# smoothieboard-alt-p1.net
KiCad netlist of a schematic drawn in Altium Designer
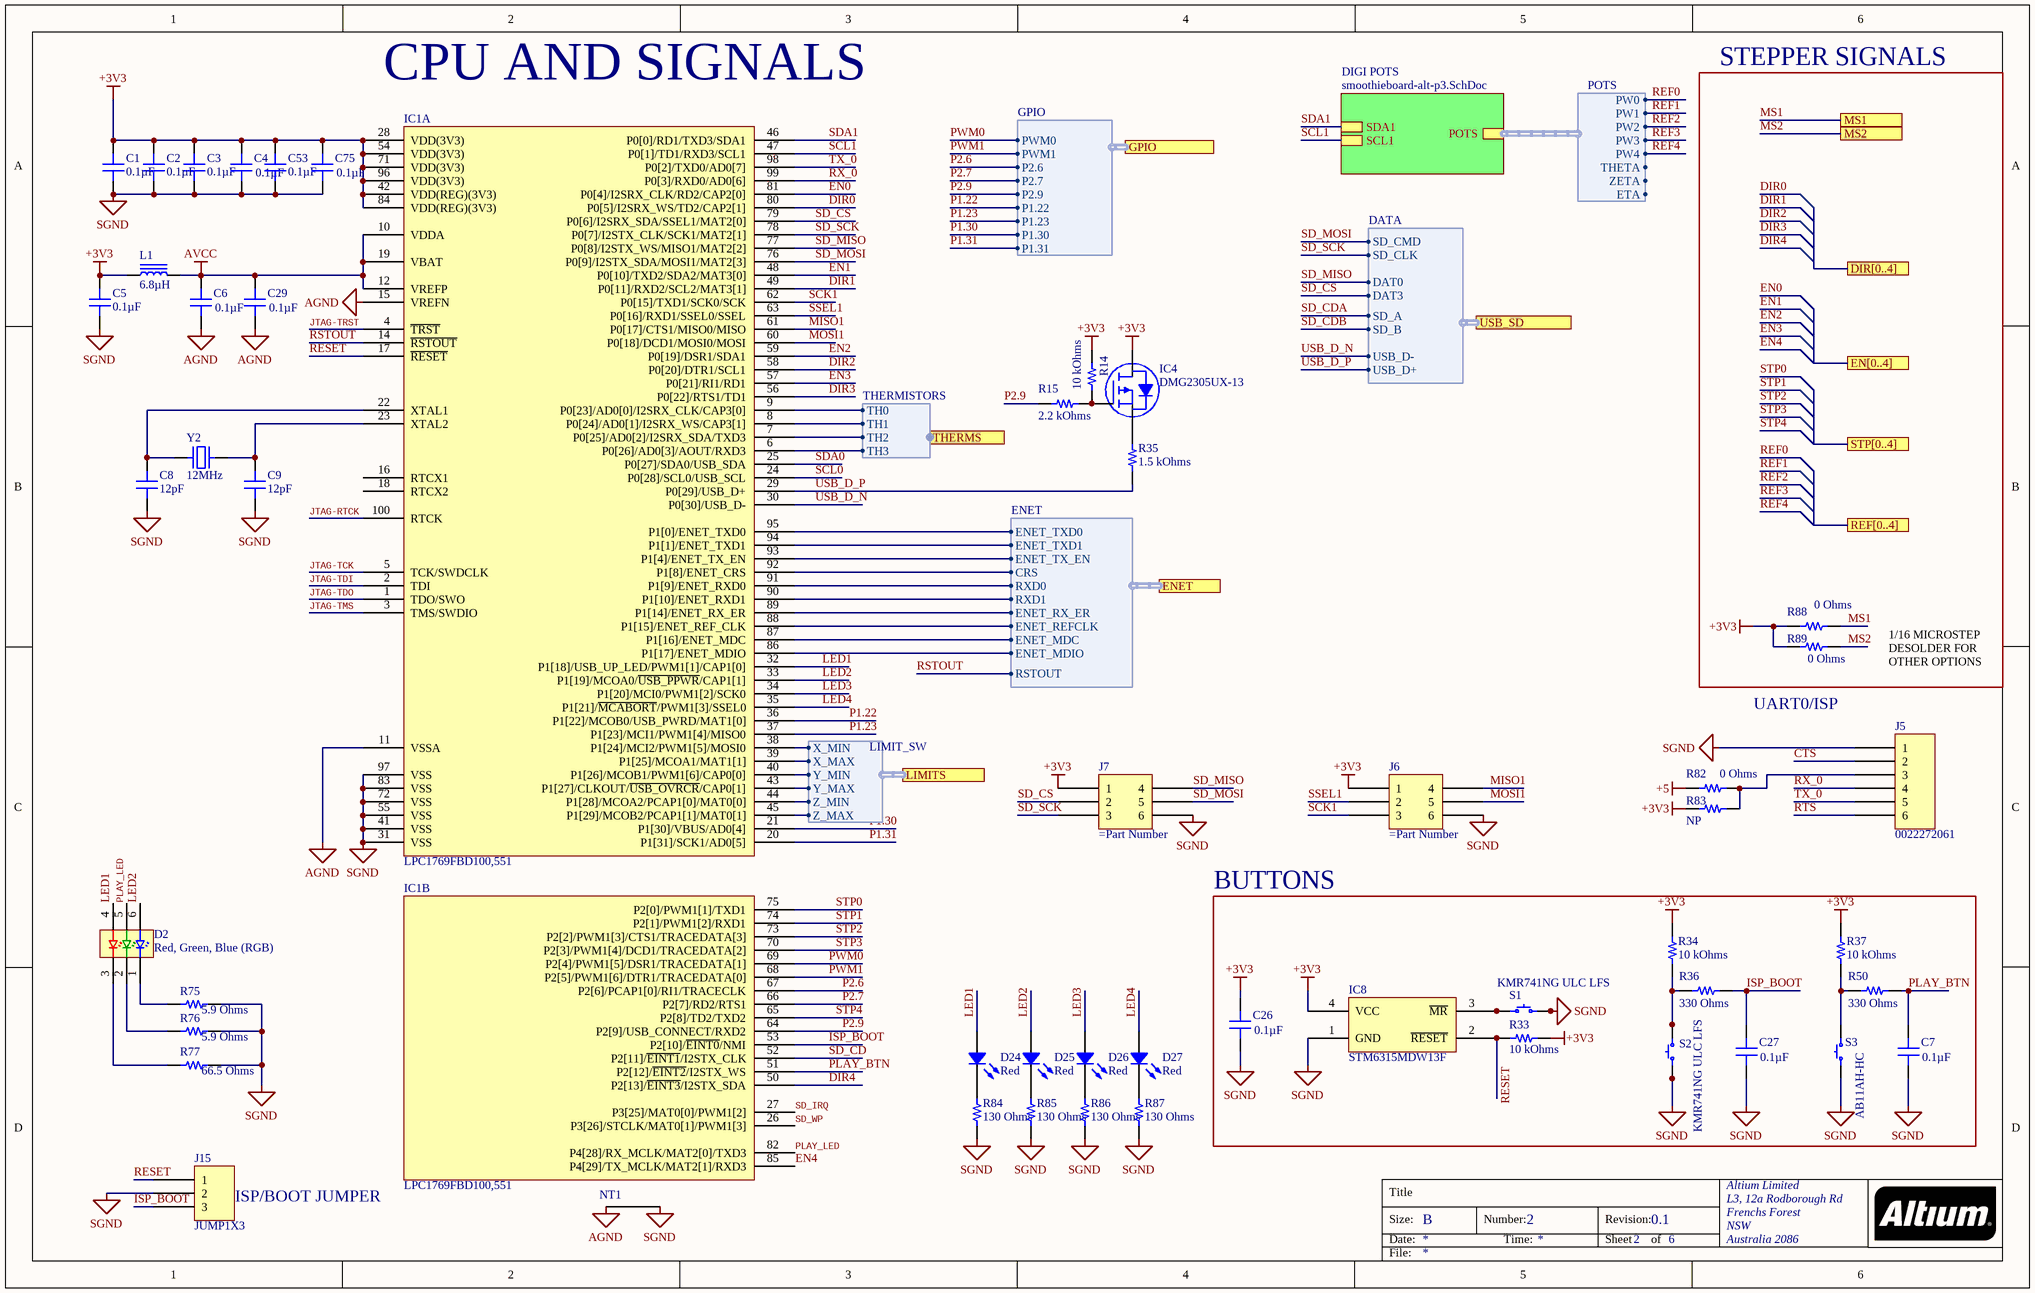
[diagram p0: smoothieboard-alt-p1.SchDoc]

(export (version "E")
  (design (tool "Eeschema 10.0.6"))
  (components
    (comp (ref "C1")
      (value "0.1µF")
      (footprint "CAP 0402_1005")
      (description "CAP CER 0.1UF 6.3V X5R 0402")
      (fields (field (name "PART NUMBER") "CC0402MRX5R5BB104") (field (name "MANUFACTURER") "Yageo"))
      (libsource (lib "CAL") (part "Capacitor"))
    )
    (comp (ref "C2")
      (value "0.1µF")
      (footprint "CAP 0402_1005")
      (description "CAP CER 0.1UF 6.3V X5R 0402")
      (fields (field (name "PART NUMBER") "CC0402MRX5R5BB104") (field (name "MANUFACTURER") "Yageo"))
      (libsource (lib "CAL") (part "Capacitor"))
    )
    (comp (ref "C3")
      (value "0.1µF")
      (footprint "CAP 0402_1005")
      (description "CAP CER 0.1UF 6.3V X5R 0402")
      (fields (field (name "PART NUMBER") "CC0402MRX5R5BB104") (field (name "MANUFACTURER") "Yageo"))
      (libsource (lib "CAL") (part "Capacitor"))
    )
    (comp (ref "C4")
      (value "0.1µF")
      (footprint "CAP 0402_1005")
      (description "CAP CER 0.1UF 6.3V X5R 0402")
      (fields (field (name "PART NUMBER") "CC0402MRX5R5BB104") (field (name "MANUFACTURER") "Yageo"))
      (libsource (lib "CAL") (part "Capacitor"))
    )
    (comp (ref "C5")
      (value "0.1µF")
      (footprint "CAP 0402_1005")
      (description "CAP CER 0.1UF 6.3V X5R 0402")
      (fields (field (name "PART NUMBER") "CC0402MRX5R5BB104") (field (name "MANUFACTURER") "Yageo"))
      (libsource (lib "CAL") (part "Capacitor"))
    )
    (comp (ref "C6")
      (value "0.1µF")
      (footprint "CAP 0402_1005")
      (description "CAP CER 0.1UF 6.3V X5R 0402")
      (fields (field (name "PART NUMBER") "CC0402MRX5R5BB104") (field (name "MANUFACTURER") "Yageo"))
      (libsource (lib "CAL") (part "Capacitor"))
    )
    (comp (ref "C7")
      (value "0.1µF")
      (footprint "CAP 0402_1005")
      (description "CAP CER 0.1UF 6.3V X5R 0402")
      (fields (field (name "PART NUMBER") "CC0402MRX5R5BB104") (field (name "MANUFACTURER") "Yageo"))
      (libsource (lib "CAL") (part "Capacitor"))
    )
    (comp (ref "C8")
      (value "12pF")
      (footprint "CAP 0402_1005")
      (description "CAP CER 12PF 10V NP0 0402")
      (fields (field (name "PART NUMBER") "C0402C120J8GAC7867") (field (name "MANUFACTURER") "KEMET"))
      (libsource (lib "CAL") (part "Capacitor"))
    )
    (comp (ref "C9")
      (value "12pF")
      (footprint "CAP 0402_1005")
      (description "CAP CER 12PF 10V NP0 0402")
      (fields (field (name "PART NUMBER") "C0402C120J8GAC7867") (field (name "MANUFACTURER") "KEMET"))
      (libsource (lib "CAL") (part "Capacitor"))
    )
    (comp (ref "C26")
      (value "0.1µF")
      (footprint "CAP 0402_1005")
      (description "CAP CER 0.1UF 6.3V X5R 0402")
      (fields (field (name "PART NUMBER") "CC0402MRX5R5BB104") (field (name "MANUFACTURER") "Yageo"))
      (libsource (lib "CAL") (part "Capacitor"))
    )
    (comp (ref "C27")
      (value "0.1µF")
      (footprint "CAP 0402_1005")
      (description "CAP CER 0.1UF 6.3V X5R 0402")
      (fields (field (name "PART NUMBER") "CC0402MRX5R5BB104") (field (name "MANUFACTURER") "Yageo"))
      (libsource (lib "CAL") (part "Capacitor"))
    )
    (comp (ref "C29")
      (value "0.1µF")
      (footprint "CAP 0402_1005")
      (description "CAP CER 0.1UF 6.3V X5R 0402")
      (fields (field (name "PART NUMBER") "CC0402MRX5R5BB104") (field (name "MANUFACTURER") "Yageo"))
      (libsource (lib "CAL") (part "Capacitor"))
    )
    (comp (ref "C53")
      (value "0.1µF")
      (footprint "CAP 0402_1005")
      (description "CAP CER 0.1UF 6.3V X5R 0402")
      (fields (field (name "PART NUMBER") "CC0402MRX5R5BB104") (field (name "MANUFACTURER") "Yageo"))
      (libsource (lib "CAL") (part "Capacitor"))
    )
    (comp (ref "C75")
      (value "0.1µF")
      (footprint "CAP 0402_1005")
      (description "CAP CER 0.1UF 6.3V X5R 0402")
      (fields (field (name "PART NUMBER") "CC0402MRX5R5BB104") (field (name "MANUFACTURER") "Yageo"))
      (libsource (lib "CAL") (part "Capacitor"))
    )
    (comp (ref "D2")
      (value "Red, Green, Blue (RGB)")
      (footprint "LED PLCC6-CREE 5.5X5.3MM")
      (description "LED RGB 6PLCC SMD")
      (fields
        (field (name "PART NUMBER") "SLV6A-FKB-CK1P1G1BB7R3R3")
        (field (name "MANUFACTURER") "Cree Inc.")
      )
      (libsource (lib "CAL") (part "RGB LED SLV6A"))
    )
    (comp (ref "D24")
      (value "Red")
      (footprint "LED 0603_1608 RED")
      (description "LED RED CLEAR 2SMD")
      (fields
        (field (name "PART NUMBER") "EAST16084RA0")
        (field (name "MANUFACTURER") "Everlight Electronics Co Ltd")
      )
      (libsource (lib "CAL") (part "LED"))
    )
    (comp (ref "D25")
      (value "Red")
      (footprint "LED 0603_1608 RED")
      (description "LED RED CLEAR 2SMD")
      (fields
        (field (name "PART NUMBER") "EAST16084RA0")
        (field (name "MANUFACTURER") "Everlight Electronics Co Ltd")
      )
      (libsource (lib "CAL") (part "LED"))
    )
    (comp (ref "D26")
      (value "Red")
      (footprint "LED 0603_1608 RED")
      (description "LED RED CLEAR 2SMD")
      (fields
        (field (name "PART NUMBER") "EAST16084RA0")
        (field (name "MANUFACTURER") "Everlight Electronics Co Ltd")
      )
      (libsource (lib "CAL") (part "LED"))
    )
    (comp (ref "D27")
      (value "Red")
      (footprint "LED 0603_1608 RED")
      (description "LED RED CLEAR 2SMD")
      (fields
        (field (name "PART NUMBER") "EAST16084RA0")
        (field (name "MANUFACTURER") "Everlight Electronics Co Ltd")
      )
      (libsource (lib "CAL") (part "LED"))
    )
    (comp (ref "IC1")
      (value "LPC1769FBD100,551")
      (footprint "NXP LQFP-100 14X14MM")
      (description "IC MCU 32BIT 512KB FLASH 100LQFP")
      (fields (field (name "MANUFACTURER") "NXP USA Inc."))
      (libsource (lib "CAL") (part "NXP LPC176X LQFP100"))
    )
    (comp (ref "IC4")
      (value "DMG2305UX-13")
      (footprint "DIODES SOT-23-3")
      (description "MOSFET P-CH 20V 4.2A SOT23")
      (fields (field (name "MANUFACTURER") "Diodes Incorporated"))
      (libsource (lib "CAL") (part "DIODES MOSFET P-CH SOT-23-3"))
    )
    (comp (ref "IC8")
      (value "STM6315MDW13F")
      (footprint "ST SOT-143-4")
      (description "IC SUPERVISOR 1 CHANNEL SOT143-4")
      (fields (field (name "MANUFACTURER") "STMicroelectronics"))
      (libsource (lib "CAL") (part "ST STM3615"))
    )
    (comp (ref "J5")
      (value "0022272061")
      (footprint "MOLEX KK 0022272061")
      (description "CONN HEADER VERT 6POS 2.54MM")
      (fields (field (name "MANUFACTURER") "Molex"))
      (libsource (lib "CAL") (part "6 Pin"))
    )
    (comp (ref "J6")
      (value "~")
      (footprint "smoothie-lib:PROG_PORT")
      (description "2x3 programming port")
      (libsource (lib "smoothie-lib") (part "PROG_PORT"))
    )
    (comp (ref "J7")
      (value "~")
      (footprint "smoothie-lib:PROG_PORT")
      (description "2x3 programming port")
      (libsource (lib "smoothie-lib") (part "PROG_PORT"))
    )
    (comp (ref "J15")
      (value "JUMP1X3")
      (footprint "smoothie-lib:JUMP1X3")
      (libsource (lib "smoothie-lib") (part "JUMP1X3"))
    )
    (comp (ref "L1")
      (value "6.8µH")
      (footprint "IND 0806_2016")
      (description "FIXED IND 6.8UH 910MA 468 MOHM")
      (fields
        (field (name "PART NUMBER") "VLS201612HBX-6R8M-1")
        (field (name "MANUFACTURER") "TDK Corporation")
      )
      (libsource (lib "CAL") (part "Inductor"))
    )
    (comp (ref "NT1")
      (value "NETTIE")
      (footprint "NETTIE")
      (description "Net tie point.")
      (libsource (lib "smoothie-lib") (part "NETTIE"))
    )
    (comp (ref "R14")
      (value "10 kOhms")
      (footprint "RES 0603_1608")
      (description "RES SMD 10K OHM 5% 1/4W 0603")
      (fields (field (name "PART NUMBER") "RCS060310K0JNEA") (field (name "MANUFACTURER") "Vishay Dale"))
      (libsource (lib "CAL") (part "Resistor"))
    )
    (comp (ref "R15")
      (value "2.2 kOhms")
      (footprint "RES 0402_1005")
      (description "RES SMD 0402 1/5W 1% 2.2K OHM")
      (fields (field (name "PART NUMBER") "SR0402FR-7T2K2L") (field (name "MANUFACTURER") "Yageo"))
      (libsource (lib "CAL") (part "Resistor"))
    )
    (comp (ref "R33")
      (value "10 kOhms")
      (footprint "RES 0603_1608")
      (description "RES SMD 10K OHM 5% 1/4W 0603")
      (fields (field (name "PART NUMBER") "RCS060310K0JNEA") (field (name "MANUFACTURER") "Vishay Dale"))
      (libsource (lib "CAL") (part "Resistor"))
    )
    (comp (ref "R34")
      (value "10 kOhms")
      (footprint "RES 0603_1608")
      (description "RES SMD 10K OHM 5% 1/4W 0603")
      (fields (field (name "PART NUMBER") "RCS060310K0JNEA") (field (name "MANUFACTURER") "Vishay Dale"))
      (libsource (lib "CAL") (part "Resistor"))
    )
    (comp (ref "R35")
      (value "1.5 kOhms")
      (footprint "RES 0402_1005")
      (description "RES SMD 1.5K OHM 1% 1/5W 0402")
      (fields (field (name "PART NUMBER") "CRCW04021K50FKEDHP") (field (name "MANUFACTURER") "Vishay Dale"))
      (libsource (lib "CAL") (part "Resistor"))
    )
    (comp (ref "R36")
      (value "330 Ohms")
      (footprint "RES 0603_1608")
      (description "RES SMD 330 OHM 5% 1/10W 0603")
      (fields
        (field (name "PART NUMBER") "ERJ-3GEYJ331V")
        (field (name "MANUFACTURER") "Panasonic Electronic Components")
      )
      (libsource (lib "CAL") (part "Resistor"))
    )
    (comp (ref "R37")
      (value "10 kOhms")
      (footprint "RES 0603_1608")
      (description "RES SMD 10K OHM 5% 1/4W 0603")
      (fields (field (name "PART NUMBER") "RCS060310K0JNEA") (field (name "MANUFACTURER") "Vishay Dale"))
      (libsource (lib "CAL") (part "Resistor"))
    )
    (comp (ref "R50")
      (value "330 Ohms")
      (footprint "RES 0603_1608")
      (description "RES SMD 330 OHM 5% 1/10W 0603")
      (fields
        (field (name "PART NUMBER") "ERJ-3GEYJ331V")
        (field (name "MANUFACTURER") "Panasonic Electronic Components")
      )
      (libsource (lib "CAL") (part "Resistor"))
    )
    (comp (ref "R75")
      (value "5.9 Ohms")
      (footprint "RES 0402_1005")
      (description "RES SMD 5.9 OHM 1% 1/16W 0402")
      (fields (field (name "PART NUMBER") "CRCW04025R90FKED") (field (name "MANUFACTURER") "Vishay Dale"))
      (libsource (lib "CAL") (part "Resistor"))
    )
    (comp (ref "R76")
      (value "5.9 Ohms")
      (footprint "RES 0402_1005")
      (description "RES SMD 5.9 OHM 1% 1/16W 0402")
      (fields (field (name "PART NUMBER") "CRCW04025R90FKED") (field (name "MANUFACTURER") "Vishay Dale"))
      (libsource (lib "CAL") (part "Resistor"))
    )
    (comp (ref "R77")
      (value "66.5 Ohms")
      (footprint "RES 0402_1005")
      (description "RES SMD 66.5 OHM 1% 1/10W 0402")
      (fields
        (field (name "PART NUMBER") "ERJ-2RKF66R5X")
        (field (name "MANUFACTURER") "Panasonic Electronic Components")
      )
      (libsource (lib "CAL") (part "Resistor"))
    )
    (comp (ref "R82")
      (value "0 Ohms")
      (footprint "RES 0603_1608")
      (description "RES SMD 0 OHM JUMPER 1/4W 0603")
      (fields (field (name "PART NUMBER") "CRCW06030000Z0EAHP") (field (name "MANUFACTURER") "Vishay Dale"))
      (libsource (lib "CAL") (part "Resistor"))
    )
    (comp (ref "R83")
      (value "NP")
      (footprint "RES 0603_1608")
      (description "RES SMD 0 OHM JUMPER 1/4W 0603")
      (fields (field (name "PART NUMBER") "CRCW06030000Z0EAHP") (field (name "MANUFACTURER") "Vishay Dale"))
      (libsource (lib "CAL") (part "Resistor"))
    )
    (comp (ref "R84")
      (value "130 Ohms")
      (footprint "RES 0402_1005")
      (description "RES SMD 130 OHM 5% 1/5W 0402")
      (fields
        (field (name "PART NUMBER") "ERJ-PA2J131X")
        (field (name "MANUFACTURER") "Panasonic Electronic Components")
      )
      (libsource (lib "CAL") (part "Resistor"))
    )
    (comp (ref "R85")
      (value "130 Ohms")
      (footprint "RES 0402_1005")
      (description "RES SMD 130 OHM 5% 1/5W 0402")
      (fields
        (field (name "PART NUMBER") "ERJ-PA2J131X")
        (field (name "MANUFACTURER") "Panasonic Electronic Components")
      )
      (libsource (lib "CAL") (part "Resistor"))
    )
    (comp (ref "R86")
      (value "130 Ohms")
      (footprint "RES 0402_1005")
      (description "RES SMD 130 OHM 5% 1/5W 0402")
      (fields
        (field (name "PART NUMBER") "ERJ-PA2J131X")
        (field (name "MANUFACTURER") "Panasonic Electronic Components")
      )
      (libsource (lib "CAL") (part "Resistor"))
    )
    (comp (ref "R87")
      (value "130 Ohms")
      (footprint "RES 0402_1005")
      (description "RES SMD 130 OHM 5% 1/5W 0402")
      (fields
        (field (name "PART NUMBER") "ERJ-PA2J131X")
        (field (name "MANUFACTURER") "Panasonic Electronic Components")
      )
      (libsource (lib "CAL") (part "Resistor"))
    )
    (comp (ref "R88")
      (value "0 Ohms")
      (footprint "RES 0603_1608")
      (description "RES SMD 0 OHM JUMPER 1/4W 0603")
      (fields (field (name "PART NUMBER") "CRCW06030000Z0EAHP") (field (name "MANUFACTURER") "Vishay Dale"))
      (libsource (lib "CAL") (part "Resistor"))
    )
    (comp (ref "R89")
      (value "0 Ohms")
      (footprint "RES 0603_1608")
      (description "RES SMD 0 OHM JUMPER 1/4W 0603")
      (fields (field (name "PART NUMBER") "CRCW06030000Z0EAHP") (field (name "MANUFACTURER") "Vishay Dale"))
      (libsource (lib "CAL") (part "Resistor"))
    )
    (comp (ref "S1")
      (value "KMR741NG ULC LFS")
      (footprint "C&K KMR7")
      (description "SWITCH TACTILE SPST-NO 50MA 32V")
      (fields (field (name "MANUFACTURER") "C&K"))
      (libsource (lib "CAL") (part "SPST-NO 4 PIN"))
    )
    (comp (ref "S2")
      (value "KMR741NG ULC LFS")
      (footprint "C&K KMR7")
      (description "SWITCH TACTILE SPST-NO 50MA 32V")
      (fields (field (name "MANUFACTURER") "C&K"))
      (libsource (lib "CAL") (part "SPST-NO 4 PIN"))
    )
    (comp (ref "S3")
      (value "AB11AH-HC")
      (footprint "NKK AB11AH-HC")
      (description "SWITCH PUSH SPST-NO 0.4VA 28V")
      (fields (field (name "MANUFACTURER") "NKK Switches"))
      (libsource (lib "CAL") (part "SPST-NO 2 PIN"))
    )
    (comp (ref "Y2")
      (value "12MHz")
      (footprint "KYOCERA CX3225GB")
      (description "CRYSTAL 12.0000MHZ 12PF SMD")
      (fields
        (field (name "PART NUMBER") "CX3225GB12000H0KPSC1")
        (field (name "MANUFACTURER") "Kyocera International Inc. Electronic Components")
      )
      (libsource (lib "CAL") (part "Kyocera Crystal CX3225GB"))
    )
  )
  (nets
    (net (code "7") (name "+3V3") (class "Default")
      (node (ref "C1") (pin "2") (pinfunction "2_2") (pintype "passive"))
      (node (ref "C2") (pin "2") (pinfunction "2_2") (pintype "passive"))
      (node (ref "C26") (pin "2") (pinfunction "2_2") (pintype "passive"))
      (node (ref "C3") (pin "2") (pinfunction "2_2") (pintype "passive"))
      (node (ref "C4") (pin "2") (pinfunction "2_2") (pintype "passive"))
      (node (ref "C5") (pin "2") (pinfunction "2_2") (pintype "passive"))
      (node (ref "C53") (pin "2") (pinfunction "2_2") (pintype "passive"))
      (node (ref "C75") (pin "2") (pinfunction "2_2") (pintype "passive"))
      (node (ref "IC1") (pin "28") (pinfunction "VDD(3V3)_28") (pintype "passive"))
      (node (ref "IC1") (pin "42") (pinfunction "VDD(REG)(3V3)_42") (pintype "passive"))
      (node (ref "IC1") (pin "54") (pinfunction "VDD(3V3)_54") (pintype "passive"))
      (node (ref "IC1") (pin "71") (pinfunction "VDD(3V3)_71") (pintype "passive"))
      (node (ref "IC1") (pin "84") (pinfunction "VDD(REG)(3V3)_84") (pintype "passive"))
      (node (ref "IC1") (pin "96") (pinfunction "VDD(3V3)_96") (pintype "passive"))
      (node (ref "IC4") (pin "3") (pinfunction "D_3") (pintype "passive"))
      (node (ref "IC8") (pin "4") (pinfunction "VCC_4") (pintype "passive"))
      (node (ref "J6") (pin "1") (pinfunction "1_1") (pintype "passive"))
      (node (ref "J7") (pin "1") (pinfunction "1_1") (pintype "passive"))
      (node (ref "L1") (pin "1") (pinfunction "1_1") (pintype "passive"))
      (node (ref "R14") (pin "1") (pinfunction "1_1") (pintype "passive"))
      (node (ref "R33") (pin "2") (pinfunction "2_2") (pintype "passive"))
      (node (ref "R34") (pin "1") (pinfunction "1_1") (pintype "passive"))
      (node (ref "R37") (pin "1") (pinfunction "1_1") (pintype "passive"))
      (node (ref "R83") (pin "1") (pinfunction "1_1") (pintype "passive"))
      (node (ref "R88") (pin "1") (pinfunction "1_1") (pintype "passive"))
      (node (ref "R89") (pin "1") (pinfunction "1_1") (pintype "passive"))
    )
    (net (code "8") (name "+5") (class "Default")
      (node (ref "R82") (pin "1") (pinfunction "1_1") (pintype "passive"))
    )
    (net (code "9") (name "/CRS") (class "Default")
      (node (ref "IC1") (pin "92") (pinfunction "P1[8]/ENET_CRS_92") (pintype "passive"))
    )
    (net (code "10") (name "/CTS") (class "Default")
      (node (ref "J5") (pin "2") (pinfunction "2_2") (pintype "passive"))
    )
    (net (code "11") (name "/DIR0") (class "Default")
      (node (ref "IC1") (pin "80") (pinfunction "P0[5]/I2SRX_WS/TD2/CAP2[1]_80") (pintype "passive"))
    )
    (net (code "12") (name "/DIR1") (class "Default")
      (node (ref "IC1") (pin "49") (pinfunction "P0[11]/RXD2/SCL2/MAT3[1]_49") (pintype "passive"))
    )
    (net (code "13") (name "/DIR2") (class "Default")
      (node (ref "IC1") (pin "58") (pinfunction "P0[20]/DTR1/SCL1_58") (pintype "passive"))
    )
    (net (code "14") (name "/DIR3") (class "Default")
      (node (ref "IC1") (pin "56") (pinfunction "P0[22]/RTS1/TD1_56") (pintype "passive"))
    )
    (net (code "15") (name "/DIR4") (class "Default")
      (node (ref "IC1") (pin "50") (pinfunction "P2[13]/~{EINT3}/I2STX_SDA_50") (pintype "passive"))
    )
    (net (code "17") (name "/EN0") (class "Default")
      (node (ref "IC1") (pin "81") (pinfunction "P0[4]/I2SRX_CLK/RD2/CAP2[0]_81") (pintype "passive"))
    )
    (net (code "18") (name "/EN1") (class "Default")
      (node (ref "IC1") (pin "48") (pinfunction "P0[10]/TXD2/SDA2/MAT3[0]_48") (pintype "passive"))
    )
    (net (code "19") (name "/EN2") (class "Default")
      (node (ref "IC1") (pin "59") (pinfunction "P0[19]/DSR1/SDA1_59") (pintype "passive"))
    )
    (net (code "20") (name "/EN3") (class "Default")
      (node (ref "IC1") (pin "57") (pinfunction "P0[21]/RI1/RD1_57") (pintype "passive"))
    )
    (net (code "21") (name "/EN4") (class "Default")
      (node (ref "IC1") (pin "85") (pinfunction "P4[29]/TX_MCLK/MAT2[1]/RXD3_85") (pintype "passive"))
    )
    (net (code "22") (name "/ENET_MDC") (class "Default")
      (node (ref "IC1") (pin "87") (pinfunction "P1[16]/ENET_MDC_87") (pintype "passive"))
    )
    (net (code "23") (name "/ENET_MDIO") (class "Default")
      (node (ref "IC1") (pin "86") (pinfunction "P1[17]/ENET_MDIO_86") (pintype "passive"))
    )
    (net (code "24") (name "/ENET_REFCLK") (class "Default")
      (node (ref "IC1") (pin "88") (pinfunction "P1[15]/ENET_REF_CLK_88") (pintype "passive"))
    )
    (net (code "25") (name "/ENET_RX_ER") (class "Default")
      (node (ref "IC1") (pin "89") (pinfunction "P1[14]/ENET_RX_ER_89") (pintype "passive"))
    )
    (net (code "26") (name "/ENET_TXD0") (class "Default")
      (node (ref "IC1") (pin "95") (pinfunction "P1[0]/ENET_TXD0_95") (pintype "passive"))
    )
    (net (code "27") (name "/ENET_TXD1") (class "Default")
      (node (ref "IC1") (pin "94") (pinfunction "P1[1]/ENET_TXD1_94") (pintype "passive"))
    )
    (net (code "28") (name "/ENET_TX_EN") (class "Default")
      (node (ref "IC1") (pin "93") (pinfunction "P1[4]/ENET_TX_EN_93") (pintype "passive"))
    )
    (net (code "30") (name "/ISP_BOOT") (class "Default")
      (node (ref "C27") (pin "2") (pinfunction "2_2") (pintype "passive"))
      (node (ref "IC1") (pin "53") (pinfunction "P2[10]/~{EINT0}/NMI_53") (pintype "passive"))
      (node (ref "J15") (pin "3") (pinfunction "3_3") (pintype "passive"))
      (node (ref "R36") (pin "1") (pinfunction "1_1") (pintype "passive"))
    )
    (net (code "31") (name "/JTAG-RTCK") (class "Default")
      (node (ref "IC1") (pin "100") (pinfunction "RTCK_100") (pintype "passive"))
    )
    (net (code "32") (name "/JTAG-TCK") (class "Default")
      (node (ref "IC1") (pin "5") (pinfunction "TCK/SWDCLK_5") (pintype "passive"))
    )
    (net (code "33") (name "/JTAG-TDI") (class "Default")
      (node (ref "IC1") (pin "2") (pinfunction "TDI_2") (pintype "passive"))
    )
    (net (code "34") (name "/JTAG-TDO") (class "Default")
      (node (ref "IC1") (pin "1") (pinfunction "TDO/SWO_1") (pintype "passive"))
    )
    (net (code "35") (name "/JTAG-TMS") (class "Default")
      (node (ref "IC1") (pin "3") (pinfunction "TMS/SWDIO_3") (pintype "passive"))
    )
    (net (code "36") (name "/JTAG-TRST") (class "Default")
      (node (ref "IC1") (pin "4") (pinfunction "~{TRST}_4") (pintype "passive"))
    )
    (net (code "37") (name "/LED1") (class "Default")
      (node (ref "D2") (pin "4") (pinfunction "A3_4") (pintype "passive"))
      (node (ref "D24") (pin "1") (pinfunction "1_1") (pintype "passive"))
      (node (ref "IC1") (pin "32") (pinfunction "P1[18]/USB_UP_LED/PWM1[1]/CAP1[0]_32") (pintype "passive"))
    )
    (net (code "38") (name "/LED2") (class "Default")
      (node (ref "D2") (pin "6") (pinfunction "A1_6") (pintype "passive"))
      (node (ref "D25") (pin "1") (pinfunction "1_1") (pintype "passive"))
      (node (ref "IC1") (pin "33") (pinfunction "P1[19]/MCOA0/~{USB_PPWR}/CAP1[1]_33") (pintype "passive"))
    )
    (net (code "39") (name "/LED3") (class "Default")
      (node (ref "D26") (pin "1") (pinfunction "1_1") (pintype "passive"))
      (node (ref "IC1") (pin "34") (pinfunction "P1[20]/MCI0/PWM1[2]/SCK0_34") (pintype "passive"))
    )
    (net (code "40") (name "/LED4") (class "Default")
      (node (ref "D27") (pin "1") (pinfunction "1_1") (pintype "passive"))
      (node (ref "IC1") (pin "35") (pinfunction "P1[21]/~{MCABORT}/PWM1[3]/SSEL0_35") (pintype "passive"))
    )
    (net (code "41") (name "/MISO1") (class "Default")
      (node (ref "IC1") (pin "61") (pinfunction "P0[17]/CTS1/MISO0/MISO_61") (pintype "passive"))
      (node (ref "J6") (pin "4") (pinfunction "4_4") (pintype "passive"))
    )
    (net (code "42") (name "/MOSI1") (class "Default")
      (node (ref "IC1") (pin "60") (pinfunction "P0[18]/DCD1/MOSI0/MOSI_60") (pintype "passive"))
      (node (ref "J6") (pin "5") (pinfunction "5_5") (pintype "passive"))
    )
    (net (code "43") (name "/MS1") (class "Default")
      (node (ref "R88") (pin "2") (pinfunction "2_2") (pintype "passive"))
    )
    (net (code "44") (name "/MS2") (class "Default")
      (node (ref "R89") (pin "2") (pinfunction "2_2") (pintype "passive"))
    )
    (net (code "45") (name "/P1.22") (class "Default")
      (node (ref "IC1") (pin "36") (pinfunction "P1[22]/MCOB0/USB_PWRD/MAT1[0]_36") (pintype "passive"))
    )
    (net (code "46") (name "/P1.23") (class "Default")
      (node (ref "IC1") (pin "37") (pinfunction "P1[23]/MCI1/PWM1[4]/MISO0_37") (pintype "passive"))
    )
    (net (code "47") (name "/P1.30") (class "Default")
      (node (ref "IC1") (pin "21") (pinfunction "P1[30]/VBUS/AD0[4]_21") (pintype "passive"))
    )
    (net (code "48") (name "/P1.31") (class "Default")
      (node (ref "IC1") (pin "20") (pinfunction "P1[31]/SCK1/AD0[5]_20") (pintype "passive"))
    )
    (net (code "49") (name "/P2.6") (class "Default")
      (node (ref "IC1") (pin "67") (pinfunction "P2[6]/PCAP1[0]/RI1/TRACECLK_67") (pintype "passive"))
    )
    (net (code "50") (name "/P2.7") (class "Default")
      (node (ref "IC1") (pin "66") (pinfunction "P2[7]/RD2/RTS1_66") (pintype "passive"))
    )
    (net (code "51") (name "/P2.9") (class "Default")
      (node (ref "IC1") (pin "64") (pinfunction "P2[9]/USB_CONNECT/RXD2_64") (pintype "passive"))
      (node (ref "R15") (pin "2") (pinfunction "2_2") (pintype "passive"))
    )
    (net (code "52") (name "/PLAY_BTN") (class "Default")
      (node (ref "C7") (pin "2") (pinfunction "2_2") (pintype "passive"))
      (node (ref "IC1") (pin "51") (pinfunction "P2[12]/~{EINT2}/I2STX_WS_51") (pintype "passive"))
      (node (ref "R50") (pin "1") (pinfunction "1_1") (pintype "passive"))
    )
    (net (code "53") (name "/PLAY_LED") (class "Default")
      (node (ref "D2") (pin "5") (pinfunction "A2_5") (pintype "passive"))
      (node (ref "IC1") (pin "82") (pinfunction "P4[28]/RX_MCLK/MAT2[0]/TXD3_82") (pintype "passive"))
    )
    (net (code "54") (name "/PWM0") (class "Default")
      (node (ref "IC1") (pin "69") (pinfunction "P2[4]/PWM1[5]/DSR1/TRACEDATA[1]_69") (pintype "passive"))
    )
    (net (code "55") (name "/PWM1") (class "Default")
      (node (ref "IC1") (pin "68") (pinfunction "P2[5]/PWM1[6]/DTR1/TRACEDATA[0]_68") (pintype "passive"))
    )
    (net (code "62") (name "/RESET") (class "Default")
      (node (ref "IC1") (pin "17") (pinfunction "~{RESET}_17") (pintype "passive"))
      (node (ref "IC8") (pin "2") (pinfunction "~{RESET}_2") (pintype "passive"))
      (node (ref "J15") (pin "1") (pinfunction "1_1") (pintype "passive"))
      (node (ref "R33") (pin "1") (pinfunction "1_1") (pintype "passive"))
    )
    (net (code "63") (name "/RSTOUT") (class "Default")
      (node (ref "IC1") (pin "14") (pinfunction "~{RSTOUT}_14") (pintype "passive"))
    )
    (net (code "64") (name "/RTS") (class "Default")
      (node (ref "J5") (pin "6") (pinfunction "6_6") (pintype "passive"))
    )
    (net (code "65") (name "/RXD0") (class "Default")
      (node (ref "IC1") (pin "91") (pinfunction "P1[9]/ENET_RXD0_91") (pintype "passive"))
    )
    (net (code "66") (name "/RXD1") (class "Default")
      (node (ref "IC1") (pin "90") (pinfunction "P1[10]/ENET_RXD1_90") (pintype "passive"))
    )
    (net (code "67") (name "/RX_0") (class "Default")
      (node (ref "IC1") (pin "99") (pinfunction "P0[3]/RXD0/AD0[6]_99") (pintype "passive"))
      (node (ref "J5") (pin "4") (pinfunction "4_4") (pintype "passive"))
    )
    (net (code "68") (name "/SCK1") (class "Default")
      (node (ref "IC1") (pin "62") (pinfunction "P0[15]/TXD1/SCK0/SCK_62") (pintype "passive"))
      (node (ref "J6") (pin "3") (pinfunction "3_3") (pintype "passive"))
    )
    (net (code "69") (name "/SCL0") (class "Default")
      (node (ref "IC1") (pin "24") (pinfunction "P0[28]/SCL0/USB_SCL_24") (pintype "passive"))
    )
    (net (code "70") (name "/SCL1") (class "Default")
      (node (ref "IC1") (pin "47") (pinfunction "P0[1]/TD1/RXD3/SCL1_47") (pintype "passive"))
    )
    (net (code "71") (name "/SDA0") (class "Default")
      (node (ref "IC1") (pin "25") (pinfunction "P0[27]/SDA0/USB_SDA_25") (pintype "passive"))
    )
    (net (code "72") (name "/SDA1") (class "Default")
      (node (ref "IC1") (pin "46") (pinfunction "P0[0]/RD1/TXD3/SDA1_46") (pintype "passive"))
    )
    (net (code "73") (name "/SD_CD") (class "Default")
      (node (ref "IC1") (pin "52") (pinfunction "P2[11]/~{EINT1}/I2STX_CLK_52") (pintype "passive"))
    )
    (net (code "76") (name "/SD_CS") (class "Default")
      (node (ref "IC1") (pin "79") (pinfunction "P0[6]/I2SRX_SDA/SSEL1/MAT2[0]_79") (pintype "passive"))
      (node (ref "J7") (pin "2") (pinfunction "2_2") (pintype "passive"))
    )
    (net (code "77") (name "/SD_IRQ") (class "Default")
      (node (ref "IC1") (pin "27") (pinfunction "P3[25]/MAT0[0]/PWM1[2]_27") (pintype "passive"))
    )
    (net (code "78") (name "/SD_MISO") (class "Default")
      (node (ref "IC1") (pin "77") (pinfunction "P0[8]/I2STX_WS/MISO1/MAT2[2]_77") (pintype "passive"))
      (node (ref "J7") (pin "4") (pinfunction "4_4") (pintype "passive"))
    )
    (net (code "79") (name "/SD_MOSI") (class "Default")
      (node (ref "IC1") (pin "76") (pinfunction "P0[9]/I2STX_SDA/MOSI1/MAT2[3]_76") (pintype "passive"))
      (node (ref "J7") (pin "5") (pinfunction "5_5") (pintype "passive"))
    )
    (net (code "80") (name "/SD_SCK") (class "Default")
      (node (ref "IC1") (pin "78") (pinfunction "P0[7]/I2STX_CLK/SCK1/MAT2[1]_78") (pintype "passive"))
      (node (ref "J7") (pin "3") (pinfunction "3_3") (pintype "passive"))
    )
    (net (code "81") (name "/SD_WP") (class "Default")
      (node (ref "IC1") (pin "26") (pinfunction "P3[26]/STCLK/MAT0[1]/PWM1[3]_26") (pintype "passive"))
    )
    (net (code "82") (name "/SSEL1") (class "Default")
      (node (ref "IC1") (pin "63") (pinfunction "P0[16]/RXD1/SSEL0/SSEL_63") (pintype "passive"))
      (node (ref "J6") (pin "2") (pinfunction "2_2") (pintype "passive"))
    )
    (net (code "83") (name "/STP0") (class "Default")
      (node (ref "IC1") (pin "75") (pinfunction "P2[0]/PWM1[1]/TXD1_75") (pintype "passive"))
    )
    (net (code "84") (name "/STP1") (class "Default")
      (node (ref "IC1") (pin "74") (pinfunction "P2[1]/PWM1[2]/RXD1_74") (pintype "passive"))
    )
    (net (code "85") (name "/STP2") (class "Default")
      (node (ref "IC1") (pin "73") (pinfunction "P2[2]/PWM1[3]/CTS1/TRACEDATA[3]_73") (pintype "passive"))
    )
    (net (code "86") (name "/STP3") (class "Default")
      (node (ref "IC1") (pin "70") (pinfunction "P2[3]/PWM1[4]/DCD1/TRACEDATA[2]_70") (pintype "passive"))
    )
    (net (code "87") (name "/STP4") (class "Default")
      (node (ref "IC1") (pin "65") (pinfunction "P2[8]/TD2/TXD2_65") (pintype "passive"))
    )
    (net (code "89") (name "/TH0") (class "Default")
      (node (ref "IC1") (pin "9") (pinfunction "P0[23]/AD0[0]/I2SRX_CLK/CAP3[0]_9") (pintype "passive"))
    )
    (net (code "90") (name "/TH1") (class "Default")
      (node (ref "IC1") (pin "8") (pinfunction "P0[24]/AD0[1]/I2SRX_WS/CAP3[1]_8") (pintype "passive"))
    )
    (net (code "91") (name "/TH2") (class "Default")
      (node (ref "IC1") (pin "7") (pinfunction "P0[25]/AD0[2]/I2SRX_SDA/TXD3_7") (pintype "passive"))
    )
    (net (code "92") (name "/TH3") (class "Default")
      (node (ref "IC1") (pin "6") (pinfunction "P0[26]/AD0[3]/AOUT/RXD3_6") (pintype "passive"))
    )
    (net (code "93") (name "/TX_0") (class "Default")
      (node (ref "IC1") (pin "98") (pinfunction "P0[2]/TXD0/AD0[7]_98") (pintype "passive"))
      (node (ref "J5") (pin "5") (pinfunction "5_5") (pintype "passive"))
    )
    (net (code "94") (name "/USB_D_N") (class "Default")
      (node (ref "IC1") (pin "30") (pinfunction "P0[30]/USB_D-_30") (pintype "passive"))
    )
    (net (code "95") (name "/USB_D_P") (class "Default")
      (node (ref "IC1") (pin "29") (pinfunction "P0[29]/USB_D+_29") (pintype "passive"))
      (node (ref "R35") (pin "1") (pinfunction "1_1") (pintype "passive"))
    )
    (net (code "96") (name "/X_MAX") (class "Default")
      (node (ref "IC1") (pin "39") (pinfunction "P1[25]/MCOA1/MAT1[1]_39") (pintype "passive"))
    )
    (net (code "97") (name "/X_MIN") (class "Default")
      (node (ref "IC1") (pin "38") (pinfunction "P1[24]/MCI2/PWM1[5]/MOSI0_38") (pintype "passive"))
    )
    (net (code "98") (name "/Y_MAX") (class "Default")
      (node (ref "IC1") (pin "43") (pinfunction "P1[27]/CLKOUT/~{USB_OVRCR}/CAP0[1]_43") (pintype "passive"))
    )
    (net (code "99") (name "/Y_MIN") (class "Default")
      (node (ref "IC1") (pin "40") (pinfunction "P1[26]/MCOB1/PWM1[6]/CAP0[0]_40") (pintype "passive"))
    )
    (net (code "100") (name "/Z_MAX") (class "Default")
      (node (ref "IC1") (pin "45") (pinfunction "P1[29]/MCOB2/PCAP1[1]/MAT0[1]_45") (pintype "passive"))
    )
    (net (code "101") (name "/Z_MIN") (class "Default")
      (node (ref "IC1") (pin "44") (pinfunction "P1[28]/MCOA2/PCAP1[0]/MAT0[0]_44") (pintype "passive"))
    )
    (net (code "108") (name "AGND") (class "Default")
      (node (ref "C29") (pin "1") (pinfunction "1_1") (pintype "passive"))
      (node (ref "C6") (pin "1") (pinfunction "1_1") (pintype "passive"))
      (node (ref "IC1") (pin "11") (pinfunction "VSSA_11") (pintype "passive"))
      (node (ref "IC1") (pin "15") (pinfunction "VREFN_15") (pintype "passive"))
      (node (ref "NT1") (pin "1") (pinfunction "1_1") (pintype "passive"))
    )
    (net (code "109") (name "AVCC") (class "Default")
      (node (ref "C29") (pin "2") (pinfunction "2_2") (pintype "passive"))
      (node (ref "C6") (pin "2") (pinfunction "2_2") (pintype "passive"))
      (node (ref "IC1") (pin "10") (pinfunction "VDDA_10") (pintype "passive"))
      (node (ref "IC1") (pin "12") (pinfunction "VREFP_12") (pintype "passive"))
      (node (ref "IC1") (pin "19") (pinfunction "VBAT_19") (pintype "passive"))
      (node (ref "L1") (pin "2") (pinfunction "2_2") (pintype "passive"))
    )
    (net (code "110") (name "Net-(D2-C1)") (class "Default")
      (node (ref "D2") (pin "1") (pinfunction "C1_1") (pintype "passive"))
      (node (ref "R75") (pin "2") (pinfunction "2_2") (pintype "passive"))
    )
    (net (code "111") (name "Net-(D2-C2)") (class "Default")
      (node (ref "D2") (pin "2") (pinfunction "C2_2") (pintype "passive"))
      (node (ref "R76") (pin "2") (pinfunction "2_2") (pintype "passive"))
    )
    (net (code "112") (name "Net-(D2-C3)") (class "Default")
      (node (ref "D2") (pin "3") (pinfunction "C3_3") (pintype "passive"))
      (node (ref "R77") (pin "2") (pinfunction "2_2") (pintype "passive"))
    )
    (net (code "113") (name "Net-(D24-Pad2)") (class "Default")
      (node (ref "D24") (pin "2") (pinfunction "2_2") (pintype "passive"))
      (node (ref "R84") (pin "2") (pinfunction "2_2") (pintype "passive"))
    )
    (net (code "114") (name "Net-(D25-Pad2)") (class "Default")
      (node (ref "D25") (pin "2") (pinfunction "2_2") (pintype "passive"))
      (node (ref "R85") (pin "2") (pinfunction "2_2") (pintype "passive"))
    )
    (net (code "115") (name "Net-(D26-Pad2)") (class "Default")
      (node (ref "D26") (pin "2") (pinfunction "2_2") (pintype "passive"))
      (node (ref "R86") (pin "2") (pinfunction "2_2") (pintype "passive"))
    )
    (net (code "116") (name "Net-(D27-Pad2)") (class "Default")
      (node (ref "D27") (pin "2") (pinfunction "2_2") (pintype "passive"))
      (node (ref "R87") (pin "2") (pinfunction "2_2") (pintype "passive"))
    )
    (net (code "117") (name "Net-(IC1A-XTAL1)") (class "Default")
      (node (ref "C8") (pin "1") (pinfunction "1_1") (pintype "passive"))
      (node (ref "IC1") (pin "22") (pinfunction "XTAL1_22") (pintype "passive"))
      (node (ref "Y2") (pin "3") (pinfunction "3_3") (pintype "passive"))
    )
    (net (code "118") (name "Net-(IC1A-XTAL2)") (class "Default")
      (node (ref "C9") (pin "1") (pinfunction "1_1") (pintype "passive"))
      (node (ref "IC1") (pin "23") (pinfunction "XTAL2_23") (pintype "passive"))
      (node (ref "Y2") (pin "1") (pinfunction "1_1") (pintype "passive"))
    )
    (net (code "119") (name "Net-(IC4-G)") (class "Default")
      (node (ref "IC4") (pin "1") (pinfunction "G_1") (pintype "passive"))
      (node (ref "R14") (pin "2") (pinfunction "2_2") (pintype "passive"))
      (node (ref "R15") (pin "1") (pinfunction "1_1") (pintype "passive"))
    )
    (net (code "120") (name "Net-(IC4-S)") (class "Default")
      (node (ref "IC4") (pin "2") (pinfunction "S_2") (pintype "passive"))
      (node (ref "R35") (pin "2") (pinfunction "2_2") (pintype "passive"))
    )
    (net (code "121") (name "Net-(IC8-~{MR})") (class "Default")
      (node (ref "IC8") (pin "3") (pinfunction "~{MR}_3") (pintype "passive"))
      (node (ref "S1") (pin "1") (pinfunction "1_1") (pintype "passive"))
      (node (ref "S1") (pin "2") (pinfunction "2_2") (pintype "passive"))
    )
    (net (code "122") (name "Net-(J5-Pad3)") (class "Default")
      (node (ref "J5") (pin "3") (pinfunction "3_3") (pintype "passive"))
      (node (ref "R82") (pin "2") (pinfunction "2_2") (pintype "passive"))
      (node (ref "R83") (pin "2") (pinfunction "2_2") (pintype "passive"))
    )
    (net (code "123") (name "Net-(R34-Pad2)") (class "Default")
      (node (ref "R34") (pin "2") (pinfunction "2_2") (pintype "passive"))
      (node (ref "R36") (pin "2") (pinfunction "2_2") (pintype "passive"))
      (node (ref "S2") (pin "3") (pinfunction "3_3") (pintype "passive"))
      (node (ref "S2") (pin "4") (pinfunction "4_4") (pintype "passive"))
    )
    (net (code "124") (name "Net-(R37-Pad2)") (class "Default")
      (node (ref "R37") (pin "2") (pinfunction "2_2") (pintype "passive"))
      (node (ref "R50") (pin "2") (pinfunction "2_2") (pintype "passive"))
      (node (ref "S3") (pin "2") (pinfunction "2_2") (pintype "passive"))
    )
    (net (code "125") (name "SGND") (class "Default")
      (node (ref "C1") (pin "1") (pinfunction "1_1") (pintype "passive"))
      (node (ref "C2") (pin "1") (pinfunction "1_1") (pintype "passive"))
      (node (ref "C26") (pin "1") (pinfunction "1_1") (pintype "passive"))
      (node (ref "C27") (pin "1") (pinfunction "1_1") (pintype "passive"))
      (node (ref "C3") (pin "1") (pinfunction "1_1") (pintype "passive"))
      (node (ref "C4") (pin "1") (pinfunction "1_1") (pintype "passive"))
      (node (ref "C5") (pin "1") (pinfunction "1_1") (pintype "passive"))
      (node (ref "C53") (pin "1") (pinfunction "1_1") (pintype "passive"))
      (node (ref "C7") (pin "1") (pinfunction "1_1") (pintype "passive"))
      (node (ref "C75") (pin "1") (pinfunction "1_1") (pintype "passive"))
      (node (ref "C8") (pin "2") (pinfunction "2_2") (pintype "passive"))
      (node (ref "C9") (pin "2") (pinfunction "2_2") (pintype "passive"))
      (node (ref "IC1") (pin "31") (pinfunction "VSS_31") (pintype "passive"))
      (node (ref "IC1") (pin "41") (pinfunction "VSS_41") (pintype "passive"))
      (node (ref "IC1") (pin "55") (pinfunction "VSS_55") (pintype "passive"))
      (node (ref "IC1") (pin "72") (pinfunction "VSS_72") (pintype "passive"))
      (node (ref "IC1") (pin "83") (pinfunction "VSS_83") (pintype "passive"))
      (node (ref "IC1") (pin "97") (pinfunction "VSS_97") (pintype "passive"))
      (node (ref "IC8") (pin "1") (pinfunction "GND_1") (pintype "passive"))
      (node (ref "J15") (pin "2") (pinfunction "2_2") (pintype "passive"))
      (node (ref "J5") (pin "1") (pinfunction "1_1") (pintype "passive"))
      (node (ref "J6") (pin "6") (pinfunction "6_6") (pintype "passive"))
      (node (ref "J7") (pin "6") (pinfunction "6_6") (pintype "passive"))
      (node (ref "NT1") (pin "2") (pinfunction "2_2") (pintype "passive"))
      (node (ref "R75") (pin "1") (pinfunction "1_1") (pintype "passive"))
      (node (ref "R76") (pin "1") (pinfunction "1_1") (pintype "passive"))
      (node (ref "R77") (pin "1") (pinfunction "1_1") (pintype "passive"))
      (node (ref "R84") (pin "1") (pinfunction "1_1") (pintype "passive"))
      (node (ref "R85") (pin "1") (pinfunction "1_1") (pintype "passive"))
      (node (ref "R86") (pin "1") (pinfunction "1_1") (pintype "passive"))
      (node (ref "R87") (pin "1") (pinfunction "1_1") (pintype "passive"))
      (node (ref "S1") (pin "3") (pinfunction "3_3") (pintype "passive"))
      (node (ref "S1") (pin "4") (pinfunction "4_4") (pintype "passive"))
      (node (ref "S2") (pin "1") (pinfunction "1_1") (pintype "passive"))
      (node (ref "S2") (pin "2") (pinfunction "2_2") (pintype "passive"))
      (node (ref "S3") (pin "1") (pinfunction "1_1") (pintype "passive"))
    )
    (net (code "126") (name "unconnected-(IC1A-RTCX1-Pad16)") (class "Default")
      (node (ref "IC1") (pin "16") (pinfunction "RTCX1_16") (pintype "passive"))
    )
    (net (code "127") (name "unconnected-(IC1A-RTCX2-Pad18)") (class "Default")
      (node (ref "IC1") (pin "18") (pinfunction "RTCX2_18") (pintype "passive"))
    )
  )
)
